# CONNECTOR_B.net
KiCad netlist of a schematic drawn in Altium Designer
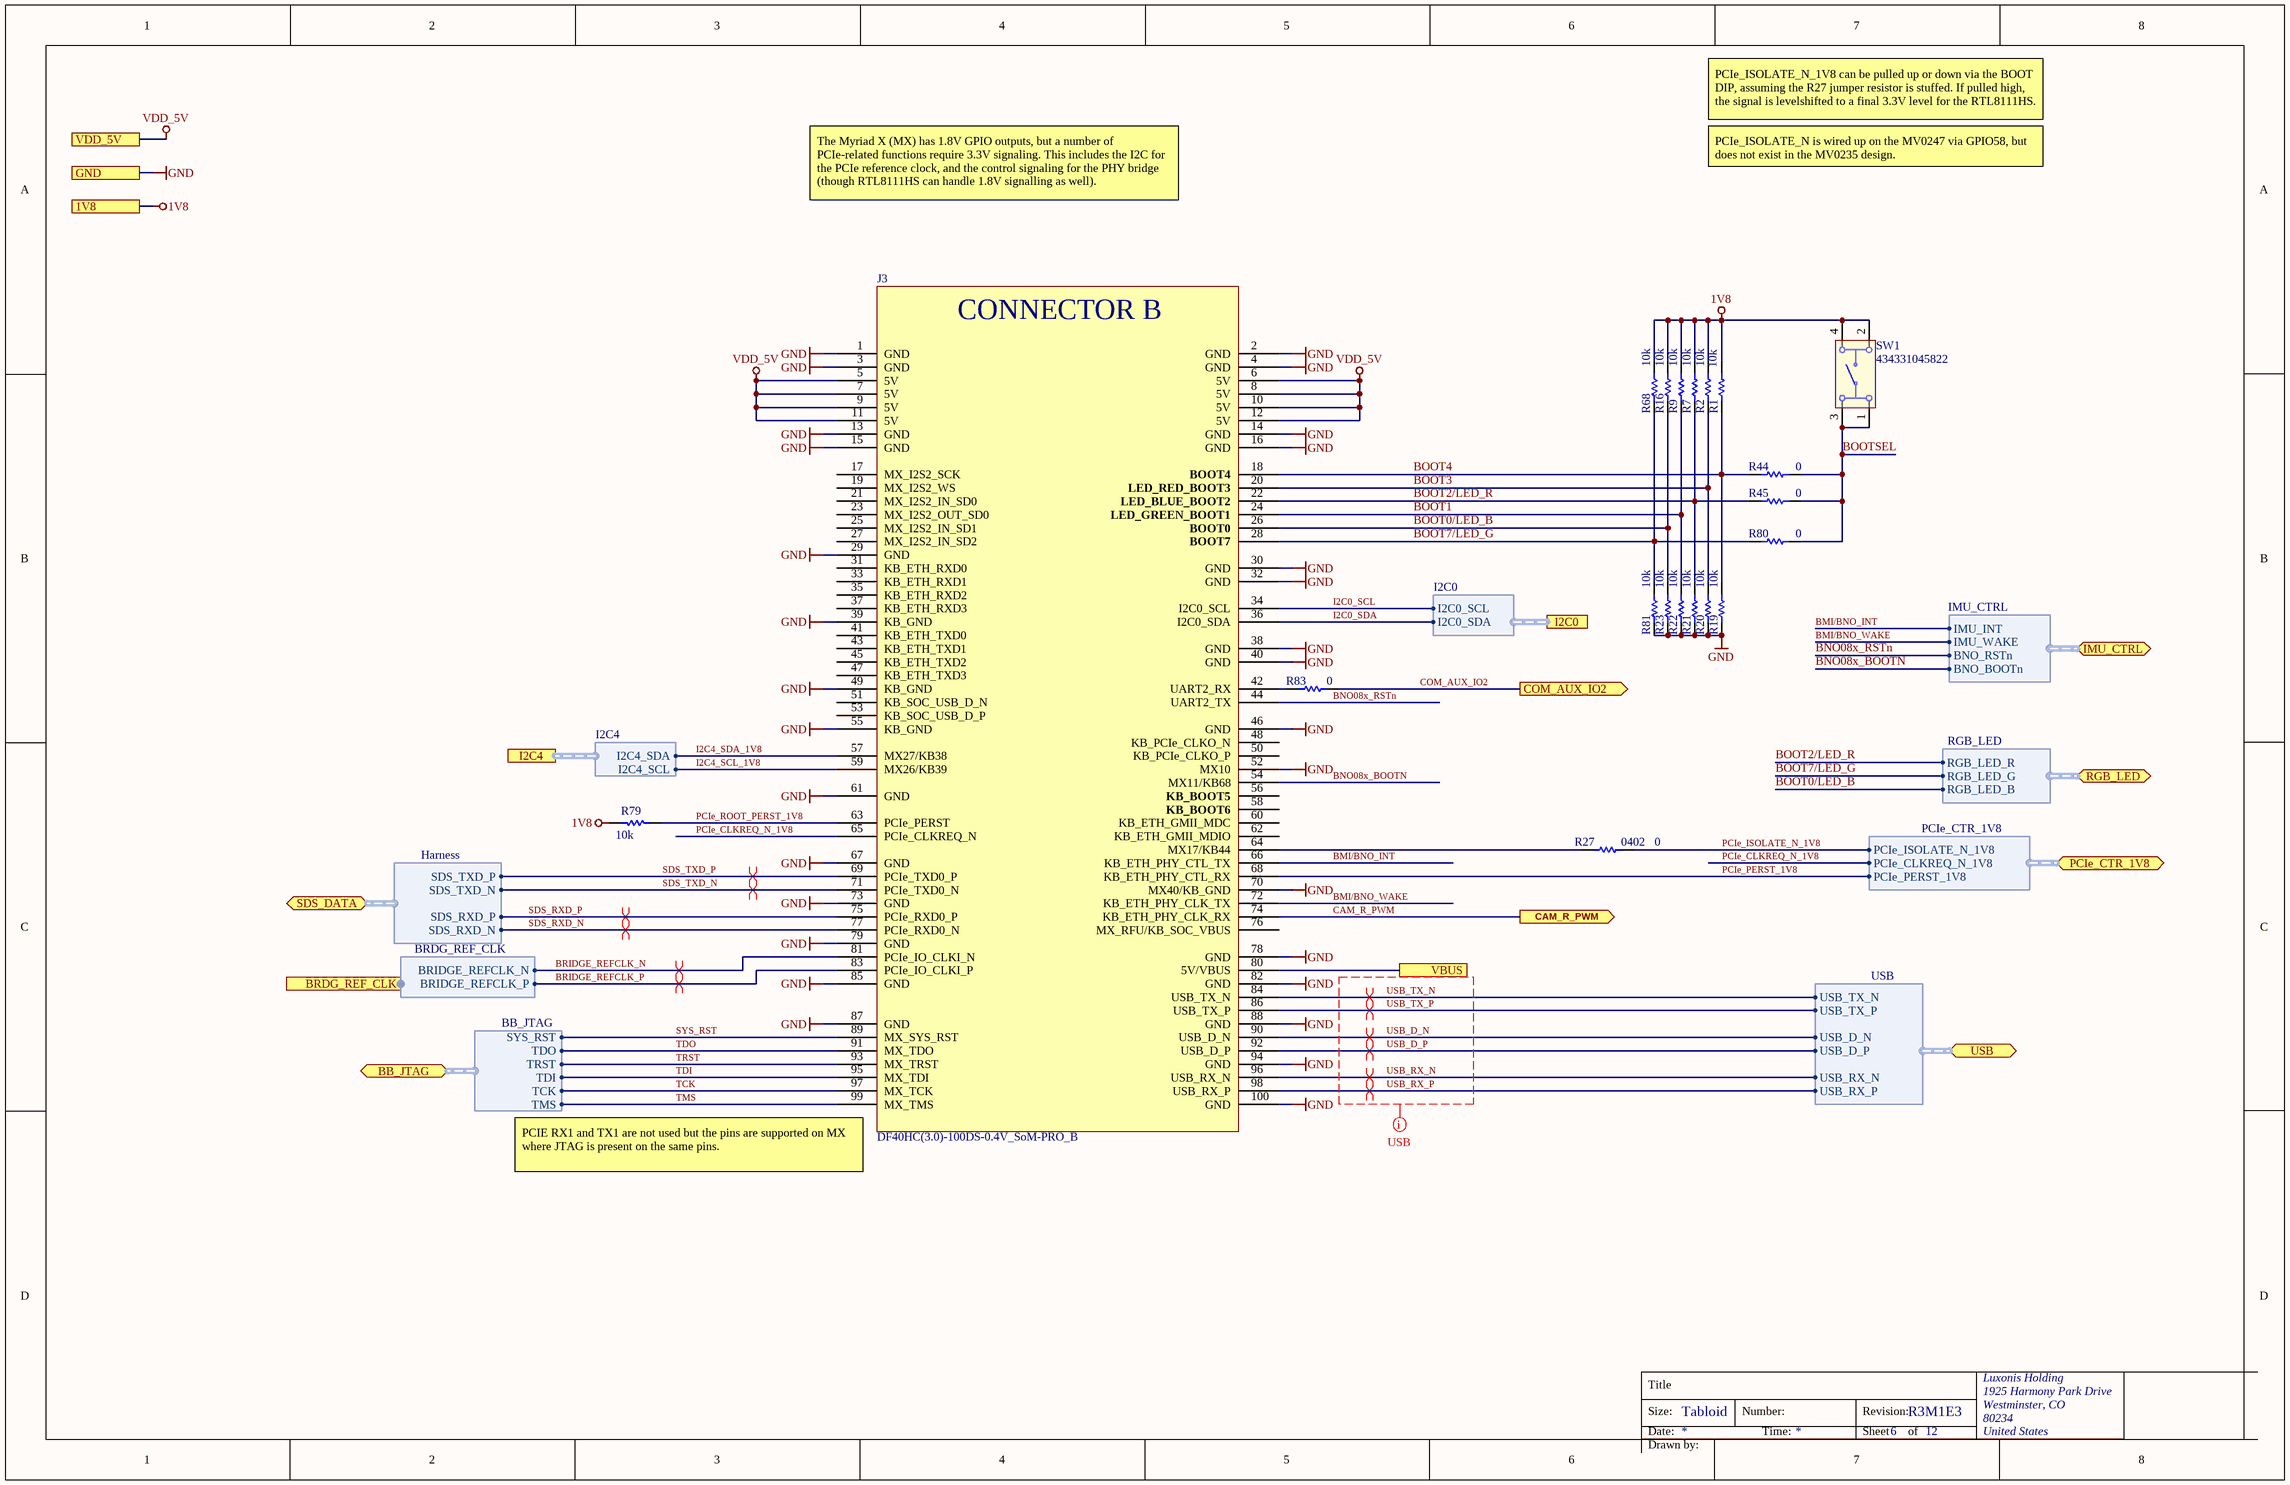
[diagram p0: CONNECTOR_B.SchDoc]

(export (version "E")
  (design (tool "Eeschema 10.0.6"))
  (components
    (comp (ref "J3")
      (value "DF40HC(3.0)-100DS-0.4V_SoM-PRO_B")
      (footprint "CON_B_BW2099_SoM_DF40HC-3.0-100DS-0.4V_minpad")
      (description "OAK-SoM-Pro_S2/S3 base board conn. B")
      (libsource (lib "Luxonis LLC") (part "DF40HC(3.0)-100DS-0.4V_SoM-PRO_B"))
    )
    (comp (ref "R1")
      (value "10k")
      (footprint "RESC0402(1005)_L")
      (description "RES SMD 10K OHM 1% 1/16W 0402")
      (fields (field (name "TOLERANCE") "1%") (field (name "Comment") "RC0402FR-1310KL"))
      (libsource (lib "Luxonis LLC") (part "RC0402FR-0722RL_1"))
    )
    (comp (ref "R2")
      (value "10k")
      (footprint "RESC0402(1005)_L")
      (description "RES SMD 10K OHM 1% 1/16W 0402")
      (fields (field (name "TOLERANCE") "1%") (field (name "Comment") "RC0402FR-1310KL"))
      (libsource (lib "Luxonis LLC") (part "RC0402FR-0722RL_1"))
    )
    (comp (ref "R7")
      (value "10k")
      (footprint "RESC0402(1005)_L")
      (description "RES SMD 10K OHM 1% 1/16W 0402")
      (fields (field (name "TOLERANCE") "1%") (field (name "Comment") "RC0402FR-1310KL"))
      (libsource (lib "Luxonis LLC") (part "RC0402FR-0722RL_1"))
    )
    (comp (ref "R9")
      (value "10k")
      (footprint "RESC0402(1005)_L")
      (description "RES SMD 10K OHM 1% 1/16W 0402")
      (fields (field (name "TOLERANCE") "1%") (field (name "Comment") "RC0402FR-1310KL"))
      (libsource (lib "Luxonis LLC") (part "RC0402FR-0722RL_1"))
    )
    (comp (ref "R16")
      (value "10k")
      (footprint "RESC0402(1005)_L")
      (description "RES SMD 10K OHM 1% 1/16W 0402")
      (fields (field (name "TOLERANCE") "1%") (field (name "Comment") "RC0402FR-1310KL"))
      (libsource (lib "Luxonis LLC") (part "RC0402FR-0722RL_1"))
    )
    (comp (ref "R19")
      (value "10k")
      (footprint "RESC0402(1005)_L")
      (description "RES SMD 10K OHM 1% 1/16W 0402")
      (fields (field (name "TOLERANCE") "1%") (field (name "Comment") "RC0402FR-1310KL"))
      (libsource (lib "Luxonis LLC") (part "RC0402FR-0722RL_1"))
    )
    (comp (ref "R20")
      (value "10k")
      (footprint "RESC0402(1005)_L")
      (description "RES SMD 10K OHM 1% 1/16W 0402")
      (fields (field (name "TOLERANCE") "1%") (field (name "Comment") "RC0402FR-1310KL"))
      (libsource (lib "Luxonis LLC") (part "RC0402FR-0722RL_1"))
    )
    (comp (ref "R21")
      (value "10k")
      (footprint "RESC0402(1005)_L")
      (description "RES SMD 10K OHM 1% 1/16W 0402")
      (fields (field (name "TOLERANCE") "1%") (field (name "Comment") "RC0402FR-1310KL"))
      (libsource (lib "Luxonis LLC") (part "RC0402FR-0722RL_1"))
    )
    (comp (ref "R22")
      (value "10k")
      (footprint "RESC0402(1005)_L")
      (description "RES SMD 10K OHM 1% 1/16W 0402")
      (fields (field (name "TOLERANCE") "1%") (field (name "Comment") "RC0402FR-1310KL"))
      (libsource (lib "Luxonis LLC") (part "RC0402FR-0722RL_1"))
    )
    (comp (ref "R23")
      (value "10k")
      (footprint "RESC0402(1005)_L")
      (description "RES SMD 10K OHM 1% 1/16W 0402")
      (fields (field (name "TOLERANCE") "1%") (field (name "Comment") "RC0402FR-1310KL"))
      (libsource (lib "Luxonis LLC") (part "RC0402FR-0722RL_1"))
    )
    (comp (ref "R27")
      (value "0")
      (footprint "RESC0402(1005)_L")
      (description "RES SMD 0 OHM 5% 1/16W 0402")
      (fields
        (field (name "CASE/PACKAGE") "0402")
        (field (name "TOLERANCE") "5%")
        (field (name "Comment") "CRCW04020000Z0ED")
      )
      (libsource (lib "Luxonis LLC") (part "Default resistor symbol"))
    )
    (comp (ref "R44")
      (value "0")
      (footprint "RESC0402(1005)_L")
      (description "RES SMD 0 OHM 5% 1/16W 0402")
      (fields (field (name "TOLERANCE") "5%") (field (name "Comment") "CRCW04020000Z0ED"))
      (libsource (lib "Luxonis LLC") (part "Default resistor symbol"))
    )
    (comp (ref "R45")
      (value "0")
      (footprint "RESC0402(1005)_L")
      (description "RES SMD 0 OHM 5% 1/16W 0402")
      (fields (field (name "TOLERANCE") "5%") (field (name "Comment") "CRCW04020000Z0ED"))
      (libsource (lib "Luxonis LLC") (part "Default resistor symbol"))
    )
    (comp (ref "R68")
      (value "10k")
      (footprint "RESC0402(1005)_L")
      (description "RES SMD 10K OHM 1% 1/16W 0402")
      (fields (field (name "TOLERANCE") "1%") (field (name "Comment") "RC0402FR-1310KL"))
      (libsource (lib "Luxonis LLC") (part "RC0402FR-0722RL_1"))
    )
    (comp (ref "R79")
      (value "10k")
      (footprint "RESC0402(1005)_N")
      (description "RES SMD 10K OHM 1% 1/16W 0402")
      (fields (field (name "TOLERANCE") "1%") (field (name "Comment") "RC0402FR-1310KL"))
      (libsource (lib "Luxonis LLC") (part "RC0402FR-0722RL_1"))
    )
    (comp (ref "R80")
      (value "0")
      (footprint "RESC0402(1005)_L")
      (description "RES SMD 0 OHM 5% 1/16W 0402")
      (fields (field (name "TOLERANCE") "5%") (field (name "Comment") "CRCW04020000Z0ED"))
      (libsource (lib "Luxonis LLC") (part "Default resistor symbol"))
    )
    (comp (ref "R81")
      (value "10k")
      (footprint "RESC0402(1005)_L")
      (description "RES SMD 10K OHM 1% 1/16W 0402")
      (fields (field (name "TOLERANCE") "1%") (field (name "Comment") "RC0402FR-1310KL"))
      (libsource (lib "Luxonis LLC") (part "RC0402FR-0722RL_1"))
    )
    (comp (ref "R83")
      (value "0")
      (footprint "RESC0402(1005)_L")
      (description "RES SMD 0 OHM 5% 1/16W 0402")
      (fields (field (name "TOLERANCE") "5%") (field (name "Comment") "CRCW04020000Z0ED"))
      (libsource (lib "Luxonis LLC") (part "Default resistor symbol"))
    )
    (comp (ref "SW1")
      (value "434331045822")
      (footprint "434331045822")
      (libsource (lib "Luxonis LLC") (part "WE-TACT-SW-4"))
    )
  )
  (nets
    (net (code "10") (name "/BMI{slash}BNO_INT") (class "Default")
      (node (ref "J3") (pin "66") (pinfunction "KB_ETH_PHY_CTL_TX_66") (pintype "passive"))
    )
    (net (code "11") (name "/BMI{slash}BNO_WAKE") (class "Default")
      (node (ref "J3") (pin "72") (pinfunction "KB_ETH_PHY_CLK_TX_72") (pintype "passive"))
    )
    (net (code "12") (name "/BNO08x_BOOTN") (class "Default")
      (node (ref "J3") (pin "54") (pinfunction "MX11/KB68_54") (pintype "passive"))
    )
    (net (code "13") (name "/BNO08x_RSTn") (class "Default")
      (node (ref "J3") (pin "44") (pinfunction "UART2_TX_44") (pintype "passive"))
    )
    (net (code "14") (name "/BOOT0{slash}LED_B") (class "Default")
      (node (ref "J3") (pin "26") (pinfunction "BOOT0_26") (pintype "passive"))
      (node (ref "R16") (pin "1") (pinfunction "1_1") (pintype "passive"))
      (node (ref "R23") (pin "2") (pinfunction "2_2") (pintype "passive"))
    )
    (net (code "15") (name "/BOOT1") (class "Default")
      (node (ref "J3") (pin "24") (pinfunction "LED_GREEN_BOOT1_24") (pintype "passive"))
      (node (ref "R22") (pin "2") (pinfunction "2_2") (pintype "passive"))
      (node (ref "R9") (pin "1") (pinfunction "1_1") (pintype "passive"))
    )
    (net (code "16") (name "/BOOT2{slash}LED_R") (class "Default")
      (node (ref "J3") (pin "22") (pinfunction "LED_BLUE_BOOT2_22") (pintype "passive"))
      (node (ref "R21") (pin "2") (pinfunction "2_2") (pintype "passive"))
      (node (ref "R45") (pin "2") (pinfunction "2_2") (pintype "passive"))
      (node (ref "R7") (pin "1") (pinfunction "1_1") (pintype "passive"))
    )
    (net (code "17") (name "/BOOT3") (class "Default")
      (node (ref "J3") (pin "20") (pinfunction "LED_RED_BOOT3_20") (pintype "passive"))
      (node (ref "R2") (pin "1") (pinfunction "1_1") (pintype "passive"))
      (node (ref "R20") (pin "2") (pinfunction "2_2") (pintype "passive"))
    )
    (net (code "18") (name "/BOOT4") (class "Default")
      (node (ref "J3") (pin "18") (pinfunction "BOOT4_18") (pintype "passive"))
      (node (ref "R1") (pin "1") (pinfunction "1_1") (pintype "passive"))
      (node (ref "R19") (pin "2") (pinfunction "2_2") (pintype "passive"))
      (node (ref "R44") (pin "2") (pinfunction "2_2") (pintype "passive"))
    )
    (net (code "19") (name "/BOOT7{slash}LED_G") (class "Default")
      (node (ref "J3") (pin "28") (pinfunction "BOOT7_28") (pintype "passive"))
      (node (ref "R68") (pin "1") (pinfunction "1_1") (pintype "passive"))
      (node (ref "R80") (pin "2") (pinfunction "2_2") (pintype "passive"))
      (node (ref "R81") (pin "2") (pinfunction "2_2") (pintype "passive"))
    )
    (net (code "20") (name "/BOOTSEL") (class "Default")
      (node (ref "R44") (pin "1") (pinfunction "1_1") (pintype "passive"))
      (node (ref "R45") (pin "1") (pinfunction "1_1") (pintype "passive"))
      (node (ref "R80") (pin "1") (pinfunction "1_1") (pintype "passive"))
      (node (ref "SW1") (pin "1") (pinfunction "1_1") (pintype "passive"))
      (node (ref "SW1") (pin "3") (pinfunction "3_3") (pintype "passive"))
    )
    (net (code "21") (name "/BRIDGE_REFCLK_N") (class "Default")
      (node (ref "J3") (pin "81") (pinfunction "PCIe_IO_CLKI_N_81") (pintype "passive"))
    )
    (net (code "22") (name "/BRIDGE_REFCLK_P") (class "Default")
      (node (ref "J3") (pin "83") (pinfunction "PCIe_IO_CLKI_P_83") (pintype "passive"))
    )
    (net (code "23") (name "/CAM_R_PWM") (class "Default")
      (node (ref "J3") (pin "74") (pinfunction "KB_ETH_PHY_CLK_RX_74") (pintype "passive"))
    )
    (net (code "24") (name "/COM_AUX_IO2") (class "Default")
      (node (ref "R83") (pin "1") (pinfunction "1_1") (pintype "passive"))
    )
    (net (code "25") (name "/I2C0_SCL") (class "Default")
      (node (ref "J3") (pin "34") (pinfunction "I2C0_SCL_34") (pintype "passive"))
    )
    (net (code "26") (name "/I2C0_SDA") (class "Default")
      (node (ref "J3") (pin "36") (pinfunction "I2C0_SDA_36") (pintype "passive"))
    )
    (net (code "27") (name "/I2C4_SCL_1V8") (class "Default")
      (node (ref "J3") (pin "59") (pinfunction "MX26/KB39_59") (pintype "passive"))
    )
    (net (code "28") (name "/I2C4_SDA_1V8") (class "Default")
      (node (ref "J3") (pin "57") (pinfunction "MX27/KB38_57") (pintype "passive"))
    )
    (net (code "29") (name "/PCIe_CLKREQ_N_1V8") (class "Default")
      (node (ref "J3") (pin "65") (pinfunction "PCIe_CLKREQ_N_65") (pintype "passive"))
    )
    (net (code "30") (name "/PCIe_ISOLATE_N_1V8") (class "Default")
      (node (ref "R27") (pin "2") (pinfunction "2_2") (pintype "passive"))
    )
    (net (code "31") (name "/PCIe_PERST_1V8") (class "Default")
      (node (ref "J3") (pin "68") (pinfunction "KB_ETH_PHY_CTL_RX_68") (pintype "passive"))
    )
    (net (code "32") (name "/PCIe_ROOT_PERST_1V8") (class "Default")
      (node (ref "J3") (pin "63") (pinfunction "PCIe_PERST_63") (pintype "passive"))
      (node (ref "R79") (pin "2") (pinfunction "2_2") (pintype "passive"))
    )
    (net (code "33") (name "/SDS_RXD_N") (class "Default")
      (node (ref "J3") (pin "77") (pinfunction "PCIe_RXD0_N_77") (pintype "passive"))
    )
    (net (code "34") (name "/SDS_RXD_P") (class "Default")
      (node (ref "J3") (pin "75") (pinfunction "PCIe_RXD0_P_75") (pintype "passive"))
    )
    (net (code "35") (name "/SDS_TXD_N") (class "Default")
      (node (ref "J3") (pin "71") (pinfunction "PCIe_TXD0_N_71") (pintype "passive"))
    )
    (net (code "36") (name "/SDS_TXD_P") (class "Default")
      (node (ref "J3") (pin "69") (pinfunction "PCIe_TXD0_P_69") (pintype "passive"))
    )
    (net (code "37") (name "/SYS_RST") (class "Default")
      (node (ref "J3") (pin "89") (pinfunction "MX_SYS_RST_89") (pintype "passive"))
    )
    (net (code "38") (name "/TCK") (class "Default")
      (node (ref "J3") (pin "97") (pinfunction "MX_TCK_97") (pintype "passive"))
    )
    (net (code "39") (name "/TDI") (class "Default")
      (node (ref "J3") (pin "95") (pinfunction "MX_TDI_95") (pintype "passive"))
    )
    (net (code "40") (name "/TDO") (class "Default")
      (node (ref "J3") (pin "91") (pinfunction "MX_TDO_91") (pintype "passive"))
    )
    (net (code "41") (name "/TMS") (class "Default")
      (node (ref "J3") (pin "99") (pinfunction "MX_TMS_99") (pintype "passive"))
    )
    (net (code "42") (name "/TRST") (class "Default")
      (node (ref "J3") (pin "93") (pinfunction "MX_TRST_93") (pintype "passive"))
    )
    (net (code "43") (name "/USB_D_N") (class "Default")
      (node (ref "J3") (pin "90") (pinfunction "USB_D_N_90") (pintype "passive"))
    )
    (net (code "44") (name "/USB_D_P") (class "Default")
      (node (ref "J3") (pin "92") (pinfunction "USB_D_P_92") (pintype "passive"))
    )
    (net (code "45") (name "/USB_RX_N") (class "Default")
      (node (ref "J3") (pin "96") (pinfunction "USB_RX_N_96") (pintype "passive"))
    )
    (net (code "46") (name "/USB_RX_P") (class "Default")
      (node (ref "J3") (pin "98") (pinfunction "USB_RX_P_98") (pintype "passive"))
    )
    (net (code "47") (name "/USB_TX_N") (class "Default")
      (node (ref "J3") (pin "84") (pinfunction "USB_TX_N_84") (pintype "passive"))
    )
    (net (code "48") (name "/USB_TX_P") (class "Default")
      (node (ref "J3") (pin "86") (pinfunction "USB_TX_P_86") (pintype "passive"))
    )
    (net (code "49") (name "/VBUS") (class "Default")
      (node (ref "J3") (pin "80") (pinfunction "5V/VBUS_80") (pintype "passive"))
    )
    (net (code "59") (name "1V8") (class "Default")
      (node (ref "R1") (pin "2") (pinfunction "2_2") (pintype "passive"))
      (node (ref "R16") (pin "2") (pinfunction "2_2") (pintype "passive"))
      (node (ref "R2") (pin "2") (pinfunction "2_2") (pintype "passive"))
      (node (ref "R68") (pin "2") (pinfunction "2_2") (pintype "passive"))
      (node (ref "R7") (pin "2") (pinfunction "2_2") (pintype "passive"))
      (node (ref "R79") (pin "1") (pinfunction "1_1") (pintype "passive"))
      (node (ref "R9") (pin "2") (pinfunction "2_2") (pintype "passive"))
      (node (ref "SW1") (pin "2") (pinfunction "2_2") (pintype "passive"))
      (node (ref "SW1") (pin "4") (pinfunction "4_4") (pintype "passive"))
    )
    (net (code "60") (name "GND") (class "Default")
      (node (ref "J3") (pin "1") (pinfunction "GND_1") (pintype "passive"))
      (node (ref "J3") (pin "100") (pinfunction "GND_100") (pintype "passive"))
      (node (ref "J3") (pin "13") (pinfunction "GND_13") (pintype "passive"))
      (node (ref "J3") (pin "14") (pinfunction "GND_14") (pintype "passive"))
      (node (ref "J3") (pin "15") (pinfunction "GND_15") (pintype "passive"))
      (node (ref "J3") (pin "16") (pinfunction "GND_16") (pintype "passive"))
      (node (ref "J3") (pin "2") (pinfunction "GND_2") (pintype "passive"))
      (node (ref "J3") (pin "29") (pinfunction "GND_29") (pintype "passive"))
      (node (ref "J3") (pin "3") (pinfunction "GND_3") (pintype "passive"))
      (node (ref "J3") (pin "30") (pinfunction "GND_30") (pintype "passive"))
      (node (ref "J3") (pin "32") (pinfunction "GND_32") (pintype "passive"))
      (node (ref "J3") (pin "38") (pinfunction "GND_38") (pintype "passive"))
      (node (ref "J3") (pin "39") (pinfunction "KB_GND_39") (pintype "passive"))
      (node (ref "J3") (pin "4") (pinfunction "GND_4") (pintype "passive"))
      (node (ref "J3") (pin "40") (pinfunction "GND_40") (pintype "passive"))
      (node (ref "J3") (pin "46") (pinfunction "GND_46") (pintype "passive"))
      (node (ref "J3") (pin "49") (pinfunction "KB_GND_49") (pintype "passive"))
      (node (ref "J3") (pin "52") (pinfunction "MX10_52") (pintype "passive"))
      (node (ref "J3") (pin "55") (pinfunction "KB_GND_55") (pintype "passive"))
      (node (ref "J3") (pin "61") (pinfunction "GND_61") (pintype "passive"))
      (node (ref "J3") (pin "67") (pinfunction "GND_67") (pintype "passive"))
      (node (ref "J3") (pin "70") (pinfunction "MX40/KB_GND_70") (pintype "passive"))
      (node (ref "J3") (pin "73") (pinfunction "GND_73") (pintype "passive"))
      (node (ref "J3") (pin "78") (pinfunction "GND_78") (pintype "passive"))
      (node (ref "J3") (pin "79") (pinfunction "GND_79") (pintype "passive"))
      (node (ref "J3") (pin "82") (pinfunction "GND_82") (pintype "passive"))
      (node (ref "J3") (pin "85") (pinfunction "GND_85") (pintype "passive"))
      (node (ref "J3") (pin "87") (pinfunction "GND_87") (pintype "passive"))
      (node (ref "J3") (pin "88") (pinfunction "GND_88") (pintype "passive"))
      (node (ref "J3") (pin "94") (pinfunction "GND_94") (pintype "passive"))
      (node (ref "R19") (pin "1") (pinfunction "1_1") (pintype "passive"))
      (node (ref "R20") (pin "1") (pinfunction "1_1") (pintype "passive"))
      (node (ref "R21") (pin "1") (pinfunction "1_1") (pintype "passive"))
      (node (ref "R22") (pin "1") (pinfunction "1_1") (pintype "passive"))
      (node (ref "R23") (pin "1") (pinfunction "1_1") (pintype "passive"))
      (node (ref "R81") (pin "1") (pinfunction "1_1") (pintype "passive"))
    )
    (net (code "61") (name "Net-(J3-MX17{slash}KB44)") (class "Default")
      (node (ref "J3") (pin "64") (pinfunction "MX17/KB44_64") (pintype "passive"))
      (node (ref "R27") (pin "1") (pinfunction "1_1") (pintype "passive"))
    )
    (net (code "62") (name "Net-(J3-UART2_RX)") (class "Default")
      (node (ref "J3") (pin "42") (pinfunction "UART2_RX_42") (pintype "passive"))
      (node (ref "R83") (pin "2") (pinfunction "2_2") (pintype "passive"))
    )
    (net (code "63") (name "VDD_5V") (class "Default")
      (node (ref "J3") (pin "10") (pinfunction "5V_10") (pintype "passive"))
      (node (ref "J3") (pin "11") (pinfunction "5V_11") (pintype "passive"))
      (node (ref "J3") (pin "12") (pinfunction "5V_12") (pintype "passive"))
      (node (ref "J3") (pin "5") (pinfunction "5V_5") (pintype "passive"))
      (node (ref "J3") (pin "6") (pinfunction "5V_6") (pintype "passive"))
      (node (ref "J3") (pin "7") (pinfunction "5V_7") (pintype "passive"))
      (node (ref "J3") (pin "8") (pinfunction "5V_8") (pintype "passive"))
      (node (ref "J3") (pin "9") (pinfunction "5V_9") (pintype "passive"))
    )
    (net (code "64") (name "unconnected-(J3-KB_BOOT5-Pad56)") (class "Default")
      (node (ref "J3") (pin "56") (pinfunction "KB_BOOT5_56") (pintype "passive"))
    )
    (net (code "65") (name "unconnected-(J3-KB_BOOT6-Pad58)") (class "Default")
      (node (ref "J3") (pin "58") (pinfunction "KB_BOOT6_58") (pintype "passive"))
    )
    (net (code "66") (name "unconnected-(J3-KB_ETH_GMII_MDC-Pad60)") (class "Default")
      (node (ref "J3") (pin "60") (pinfunction "KB_ETH_GMII_MDC_60") (pintype "passive"))
    )
    (net (code "67") (name "unconnected-(J3-KB_ETH_GMII_MDIO-Pad62)") (class "Default")
      (node (ref "J3") (pin "62") (pinfunction "KB_ETH_GMII_MDIO_62") (pintype "passive"))
    )
    (net (code "68") (name "unconnected-(J3-KB_ETH_RXD0-Pad31)") (class "Default")
      (node (ref "J3") (pin "31") (pinfunction "KB_ETH_RXD0_31") (pintype "passive"))
    )
    (net (code "69") (name "unconnected-(J3-KB_ETH_RXD1-Pad33)") (class "Default")
      (node (ref "J3") (pin "33") (pinfunction "KB_ETH_RXD1_33") (pintype "passive"))
    )
    (net (code "70") (name "unconnected-(J3-KB_ETH_RXD2-Pad35)") (class "Default")
      (node (ref "J3") (pin "35") (pinfunction "KB_ETH_RXD2_35") (pintype "passive"))
    )
    (net (code "71") (name "unconnected-(J3-KB_ETH_RXD3-Pad37)") (class "Default")
      (node (ref "J3") (pin "37") (pinfunction "KB_ETH_RXD3_37") (pintype "passive"))
    )
    (net (code "72") (name "unconnected-(J3-KB_ETH_TXD0-Pad41)") (class "Default")
      (node (ref "J3") (pin "41") (pinfunction "KB_ETH_TXD0_41") (pintype "passive"))
    )
    (net (code "73") (name "unconnected-(J3-KB_ETH_TXD1-Pad43)") (class "Default")
      (node (ref "J3") (pin "43") (pinfunction "KB_ETH_TXD1_43") (pintype "passive"))
    )
    (net (code "74") (name "unconnected-(J3-KB_ETH_TXD2-Pad45)") (class "Default")
      (node (ref "J3") (pin "45") (pinfunction "KB_ETH_TXD2_45") (pintype "passive"))
    )
    (net (code "75") (name "unconnected-(J3-KB_ETH_TXD3-Pad47)") (class "Default")
      (node (ref "J3") (pin "47") (pinfunction "KB_ETH_TXD3_47") (pintype "passive"))
    )
    (net (code "76") (name "unconnected-(J3-KB_PCIe_CLKO_N-Pad48)") (class "Default")
      (node (ref "J3") (pin "48") (pinfunction "KB_PCIe_CLKO_N_48") (pintype "passive"))
    )
    (net (code "77") (name "unconnected-(J3-KB_PCIe_CLKO_P-Pad50)") (class "Default")
      (node (ref "J3") (pin "50") (pinfunction "KB_PCIe_CLKO_P_50") (pintype "passive"))
    )
    (net (code "78") (name "unconnected-(J3-KB_SOC_USB_D_N-Pad51)") (class "Default")
      (node (ref "J3") (pin "51") (pinfunction "KB_SOC_USB_D_N_51") (pintype "passive"))
    )
    (net (code "79") (name "unconnected-(J3-KB_SOC_USB_D_P-Pad53)") (class "Default")
      (node (ref "J3") (pin "53") (pinfunction "KB_SOC_USB_D_P_53") (pintype "passive"))
    )
    (net (code "80") (name "unconnected-(J3-MX_I2S2_IN_SD0-Pad21)") (class "Default")
      (node (ref "J3") (pin "21") (pinfunction "MX_I2S2_IN_SD0_21") (pintype "passive"))
    )
    (net (code "81") (name "unconnected-(J3-MX_I2S2_IN_SD1-Pad25)") (class "Default")
      (node (ref "J3") (pin "25") (pinfunction "MX_I2S2_IN_SD1_25") (pintype "passive"))
    )
    (net (code "82") (name "unconnected-(J3-MX_I2S2_IN_SD2-Pad27)") (class "Default")
      (node (ref "J3") (pin "27") (pinfunction "MX_I2S2_IN_SD2_27") (pintype "passive"))
    )
    (net (code "83") (name "unconnected-(J3-MX_I2S2_OUT_SD0-Pad23)") (class "Default")
      (node (ref "J3") (pin "23") (pinfunction "MX_I2S2_OUT_SD0_23") (pintype "passive"))
    )
    (net (code "84") (name "unconnected-(J3-MX_I2S2_SCK-Pad17)") (class "Default")
      (node (ref "J3") (pin "17") (pinfunction "MX_I2S2_SCK_17") (pintype "passive"))
    )
    (net (code "85") (name "unconnected-(J3-MX_I2S2_WS-Pad19)") (class "Default")
      (node (ref "J3") (pin "19") (pinfunction "MX_I2S2_WS_19") (pintype "passive"))
    )
    (net (code "86") (name "unconnected-(J3-MX_RFU{slash}KB_SOC_VBUS-Pad76)") (class "Default")
      (node (ref "J3") (pin "76") (pinfunction "MX_RFU/KB_SOC_VBUS_76") (pintype "passive"))
    )
  )
)
